# mini-MIDI-Splitter.net
KiCad netlist of a schematic drawn in EAGLE
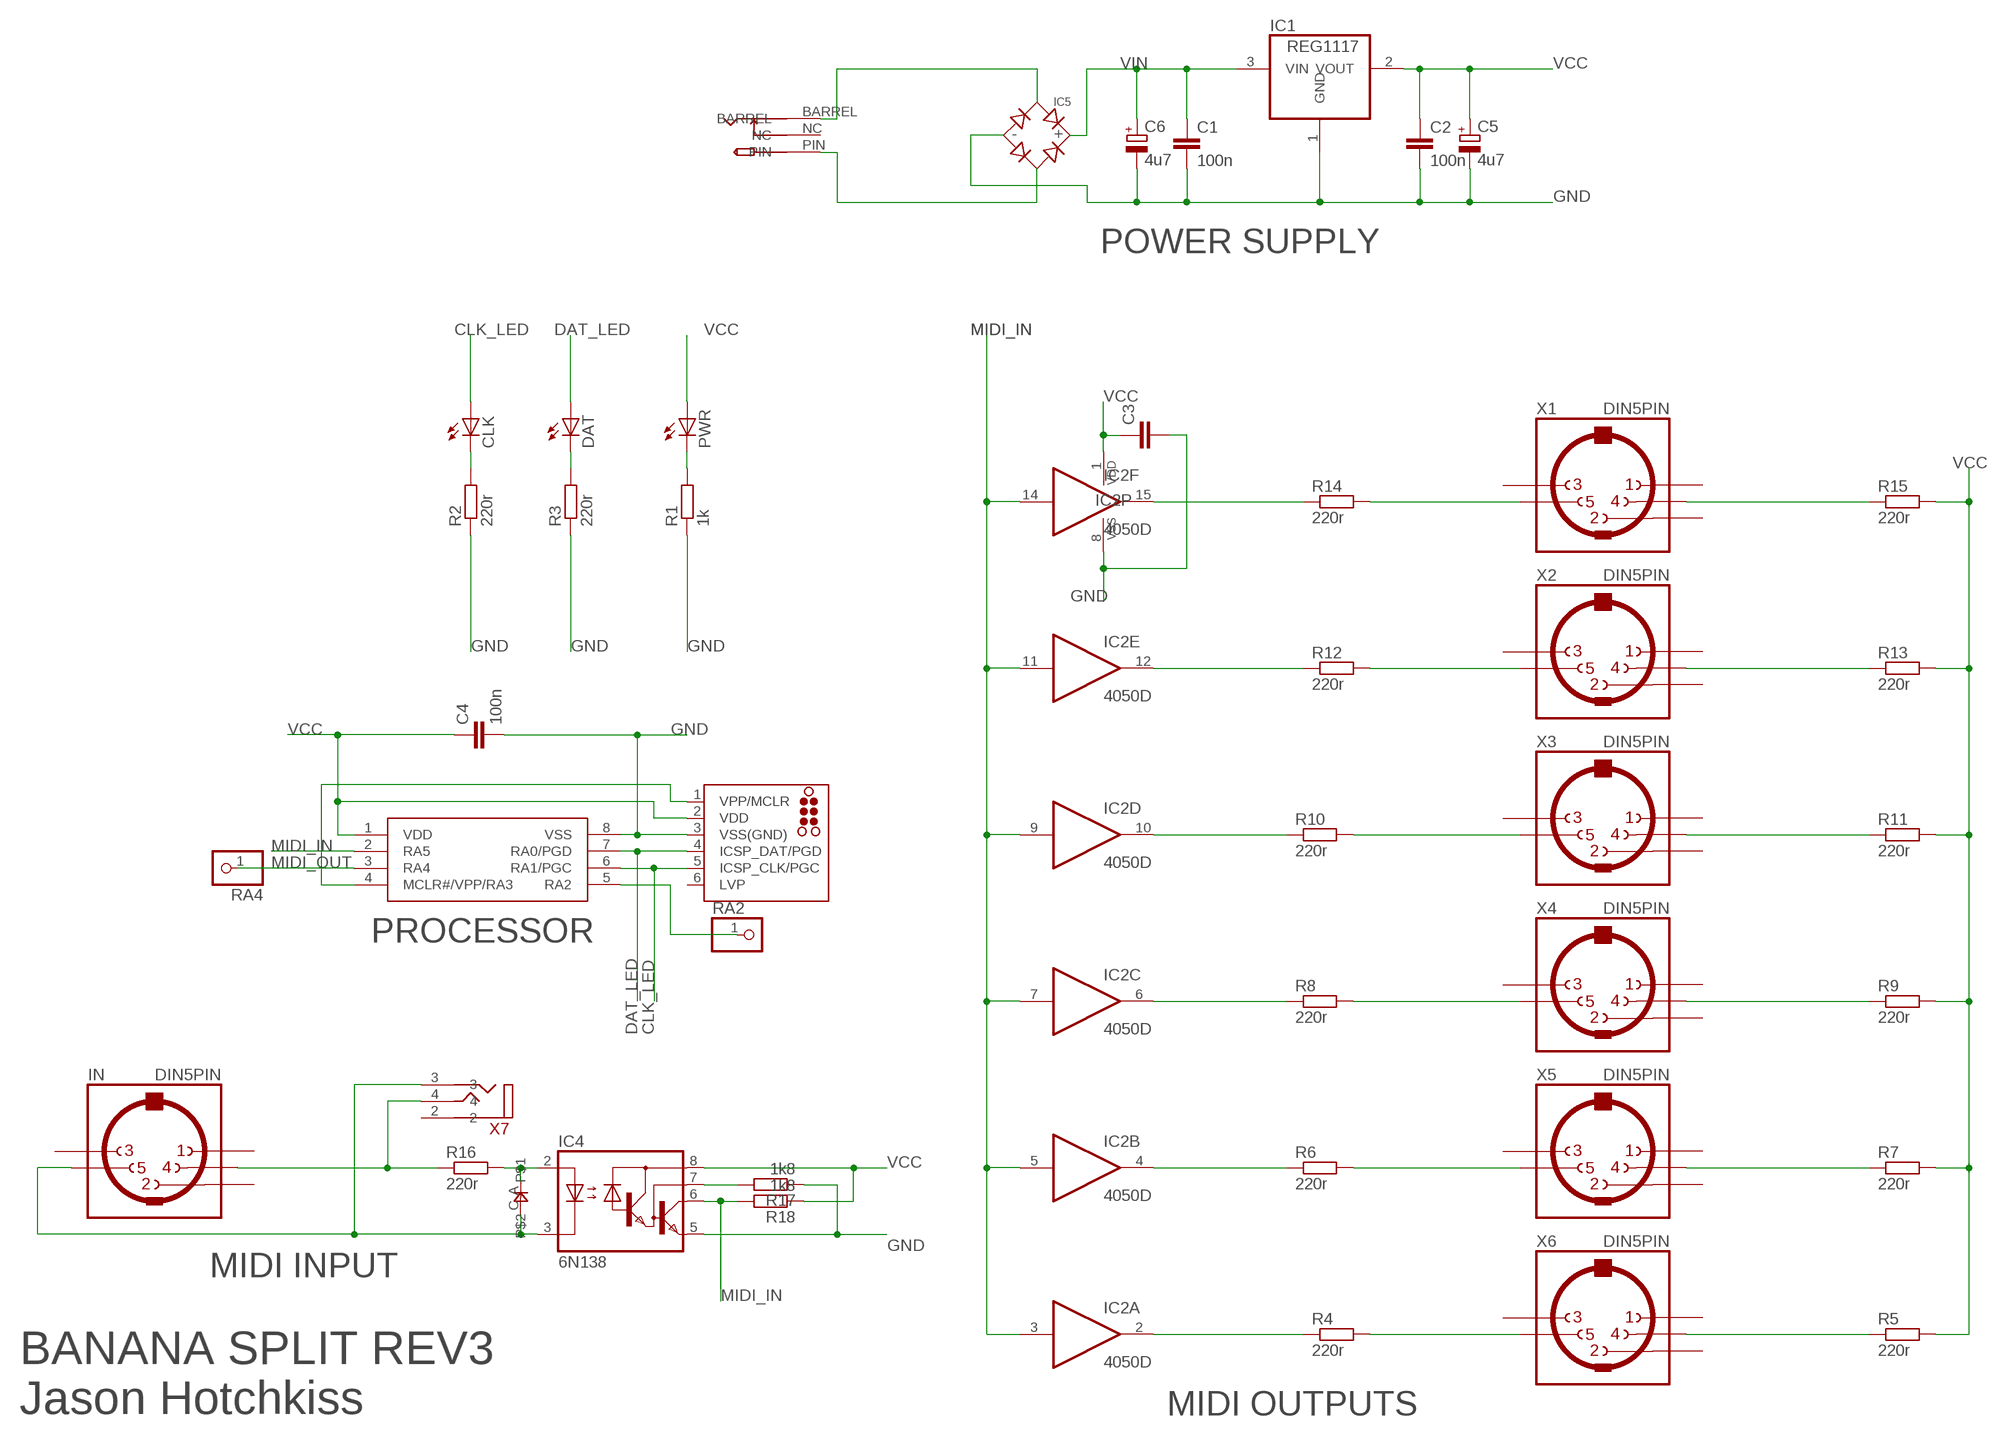
[diagram p0: schematic, sheet 1]

(export (version "E")
  (design (tool "Eeschema 10.0.6"))
  (components
    (comp (ref "C1")
      (value "100n")
      (footprint "eagle-import:C0805")
      (libsource (lib "eagle-import") (part "C-EUC0805"))
    )
    (comp (ref "C2")
      (value "100n")
      (footprint "eagle-import:C0805")
      (libsource (lib "eagle-import") (part "C-EUC0805"))
    )
    (comp (ref "C3")
      (value "C-EUC0805")
      (footprint "eagle-import:C0805")
      (libsource (lib "eagle-import") (part "C-EUC0805"))
    )
    (comp (ref "C4")
      (value "100n")
      (footprint "eagle-import:C0805")
      (libsource (lib "eagle-import") (part "C-EUC0805"))
    )
    (comp (ref "C5")
      (value "4u7")
      (footprint "eagle-import:E2-4")
      (libsource (lib "eagle-import") (part "CPOL-EUE2-4"))
    )
    (comp (ref "C6")
      (value "4u7")
      (footprint "eagle-import:E2-4")
      (libsource (lib "eagle-import") (part "CPOL-EUE2-4"))
    )
    (comp (ref "CLK")
      (value "LED3MM")
      (footprint "eagle-import:LED3MM")
      (libsource (lib "eagle-import") (part "LED3MM"))
    )
    (comp (ref "D1")
      (value "0805DIODE")
      (footprint "eagle-import:0805DIODE")
      (libsource (lib "eagle-import") (part "0805DIODE"))
    )
    (comp (ref "DAT")
      (value "LED3MM")
      (footprint "eagle-import:LED3MM")
      (libsource (lib "eagle-import") (part "LED3MM"))
    )
    (comp (ref "IC1")
      (value "REG1117")
      (footprint "eagle-import:SOT223")
      (libsource (lib "eagle-import") (part "REG1117"))
    )
    (comp (ref "IC2")
      (value "4050D")
      (footprint "eagle-import:SO16")
      (libsource (lib "eagle-import") (part "4050D"))
    )
    (comp (ref "IC3")
      (value "PIC12F1822SO08")
      (footprint "eagle-import:SO08")
      (libsource (lib "eagle-import") (part "PIC12F1822SO08"))
    )
    (comp (ref "IC4")
      (value "6N138")
      (footprint "eagle-import:DIL08")
      (fields (field (name "MF") "VISHAY/TELEFUNKEN"))
      (libsource (lib "eagle-import") (part "6N138"))
    )
    (comp (ref "IC5")
      (value "BRIDGERECTIFIER")
      (footprint "eagle-import:SOIC-4")
      (libsource (lib "eagle-import") (part "BRIDGERECTIFIER"))
    )
    (comp (ref "ICSP")
      (value "TC2030-MCP-NL")
      (footprint "eagle-import:TC2030-MCP-NL")
      (libsource (lib "eagle-import") (part "TC2030-MCP-NL"))
    )
    (comp (ref "IN")
      (value "DIN5PIN")
      (footprint "eagle-import:EDGEDIN")
      (libsource (lib "eagle-import") (part "DIN5PIN"))
    )
    (comp (ref "PWR")
      (value "LED3MM")
      (footprint "eagle-import:LED3MM")
      (libsource (lib "eagle-import") (part "LED3MM"))
    )
    (comp (ref "R1")
      (value "1k")
      (footprint "eagle-import:R0805")
      (libsource (lib "eagle-import") (part "R-EU_R0805"))
    )
    (comp (ref "R2")
      (value "220r")
      (footprint "eagle-import:R0805")
      (libsource (lib "eagle-import") (part "R-EU_R0805"))
    )
    (comp (ref "R3")
      (value "220r")
      (footprint "eagle-import:R0805")
      (libsource (lib "eagle-import") (part "R-EU_R0805"))
    )
    (comp (ref "R4")
      (value "220r")
      (footprint "eagle-import:R0805")
      (libsource (lib "eagle-import") (part "R-EU_R0805"))
    )
    (comp (ref "R5")
      (value "220r")
      (footprint "eagle-import:R0805")
      (libsource (lib "eagle-import") (part "R-EU_R0805"))
    )
    (comp (ref "R6")
      (value "220r")
      (footprint "eagle-import:R0805")
      (libsource (lib "eagle-import") (part "R-EU_R0805"))
    )
    (comp (ref "R7")
      (value "220r")
      (footprint "eagle-import:R0805")
      (libsource (lib "eagle-import") (part "R-EU_R0805"))
    )
    (comp (ref "R8")
      (value "220r")
      (footprint "eagle-import:R0805")
      (libsource (lib "eagle-import") (part "R-EU_R0805"))
    )
    (comp (ref "R9")
      (value "220r")
      (footprint "eagle-import:R0805")
      (libsource (lib "eagle-import") (part "R-EU_R0805"))
    )
    (comp (ref "R10")
      (value "220r")
      (footprint "eagle-import:R0805")
      (libsource (lib "eagle-import") (part "R-EU_R0805"))
    )
    (comp (ref "R11")
      (value "220r")
      (footprint "eagle-import:R0805")
      (libsource (lib "eagle-import") (part "R-EU_R0805"))
    )
    (comp (ref "R12")
      (value "220r")
      (footprint "eagle-import:R0805")
      (libsource (lib "eagle-import") (part "R-EU_R0805"))
    )
    (comp (ref "R13")
      (value "220r")
      (footprint "eagle-import:R0805")
      (libsource (lib "eagle-import") (part "R-EU_R0805"))
    )
    (comp (ref "R14")
      (value "220r")
      (footprint "eagle-import:R0805")
      (libsource (lib "eagle-import") (part "R-EU_R0805"))
    )
    (comp (ref "R15")
      (value "220r")
      (footprint "eagle-import:R0805")
      (libsource (lib "eagle-import") (part "R-EU_R0805"))
    )
    (comp (ref "R16")
      (value "220r")
      (footprint "eagle-import:R0805")
      (libsource (lib "eagle-import") (part "R-EU_R0805"))
    )
    (comp (ref "R17")
      (value "1k8")
      (footprint "eagle-import:R0805")
      (libsource (lib "eagle-import") (part "R-EU_R0805"))
    )
    (comp (ref "R18")
      (value "1k8")
      (footprint "eagle-import:R0805")
      (libsource (lib "eagle-import") (part "R-EU_R0805"))
    )
    (comp (ref "RA2")
      (value "PINHD-1X1")
      (footprint "eagle-import:1X01")
      (libsource (lib "eagle-import") (part "PINHD-1X1"))
    )
    (comp (ref "RA4")
      (value "PINHD-1X1")
      (footprint "eagle-import:1X01")
      (libsource (lib "eagle-import") (part "PINHD-1X1"))
    )
    (comp (ref "U$1")
      (value "PWR_SOCKET_2_1MM")
      (footprint "eagle-import:PWR_SOCKET_2_1MM")
      (libsource (lib "eagle-import") (part "PWR_SOCKET_2_1MM"))
    )
    (comp (ref "X1")
      (value "DIN5PIN")
      (footprint "eagle-import:EDGEDIN")
      (libsource (lib "eagle-import") (part "DIN5PIN"))
    )
    (comp (ref "X2")
      (value "DIN5PIN")
      (footprint "eagle-import:EDGEDIN")
      (libsource (lib "eagle-import") (part "DIN5PIN"))
    )
    (comp (ref "X3")
      (value "DIN5PIN")
      (footprint "eagle-import:EDGEDIN")
      (libsource (lib "eagle-import") (part "DIN5PIN"))
    )
    (comp (ref "X4")
      (value "DIN5PIN")
      (footprint "eagle-import:EDGEDIN")
      (libsource (lib "eagle-import") (part "DIN5PIN"))
    )
    (comp (ref "X5")
      (value "DIN5PIN")
      (footprint "eagle-import:EDGEDIN")
      (libsource (lib "eagle-import") (part "DIN5PIN"))
    )
    (comp (ref "X6")
      (value "DIN5PIN")
      (footprint "eagle-import:EDGEDIN")
      (libsource (lib "eagle-import") (part "DIN5PIN"))
    )
    (comp (ref "X7")
      (value "VERTICAL_3_5MM_SOCKET")
      (footprint "eagle-import:VERTICAL_3_5MM_SOCKET")
      (libsource (lib "eagle-import") (part "VERTICAL_3_5MM_SOCKET"))
    )
  )
  (nets
    (net (code "1") (name "/CLK_LED") (class "Default")
      (node (ref "CLK") (pin "A") (pinfunction "A_A") (pintype "passive"))
      (node (ref "IC3") (pin "6") (pinfunction "RA1/PGC_6") (pintype "bidirectional"))
      (node (ref "ICSP") (pin "5") (pinfunction "ICSP_CLK/PGC_5") (pintype "output"))
    )
    (net (code "2") (name "/DAT_LED") (class "Default")
      (node (ref "DAT") (pin "A") (pinfunction "A_A") (pintype "passive"))
      (node (ref "IC3") (pin "7") (pinfunction "RA0/PGD_7") (pintype "bidirectional"))
      (node (ref "ICSP") (pin "4") (pinfunction "ICSP_DAT/PGD_4") (pintype "bidirectional"))
    )
    (net (code "3") (name "/GND") (class "Default")
      (node (ref "C1") (pin "2") (pinfunction "2_2") (pintype "passive"))
      (node (ref "C2") (pin "2") (pinfunction "2_2") (pintype "passive"))
      (node (ref "C3") (pin "2") (pinfunction "2_2") (pintype "passive"))
      (node (ref "C4") (pin "2") (pinfunction "2_2") (pintype "passive"))
      (node (ref "C5") (pin "-") (pinfunction "-_-") (pintype "passive"))
      (node (ref "C6") (pin "-") (pinfunction "-_-") (pintype "passive"))
      (node (ref "IC1") (pin "1") (pinfunction "GND_1") (pintype "power_in"))
      (node (ref "IC2") (pin "8") (pinfunction "VSS_8") (pintype "power_in"))
      (node (ref "IC3") (pin "8") (pinfunction "VSS_8") (pintype "power_in"))
      (node (ref "IC4") (pin "5") (pinfunction "GND_5") (pintype "passive"))
      (node (ref "IC5") (pin "-") (pinfunction "-_-") (pintype "passive"))
      (node (ref "ICSP") (pin "3") (pinfunction "VSS(GND)_3") (pintype "power_in"))
      (node (ref "R1") (pin "1") (pinfunction "1_1") (pintype "passive"))
      (node (ref "R17") (pin "1") (pinfunction "1_1") (pintype "passive"))
      (node (ref "R2") (pin "1") (pinfunction "1_1") (pintype "passive"))
      (node (ref "R3") (pin "1") (pinfunction "1_1") (pintype "passive"))
    )
    (net (code "4") (name "/MIDI_IN") (class "Default")
      (node (ref "IC2") (pin "11") (pinfunction "I_11") (pintype "input"))
      (node (ref "IC2") (pin "14") (pinfunction "I_14") (pintype "input"))
      (node (ref "IC2") (pin "3") (pinfunction "I_3") (pintype "input"))
      (node (ref "IC2") (pin "5") (pinfunction "I_5") (pintype "input"))
      (node (ref "IC2") (pin "7") (pinfunction "I_7") (pintype "input"))
      (node (ref "IC2") (pin "9") (pinfunction "I_9") (pintype "input"))
      (node (ref "IC3") (pin "2") (pinfunction "RA5_2") (pintype "bidirectional"))
      (node (ref "IC4") (pin "6") (pinfunction "VO_6") (pintype "passive"))
      (node (ref "R18") (pin "2") (pinfunction "2_2") (pintype "passive"))
    )
    (net (code "5") (name "/MIDI_OUT") (class "Default")
      (node (ref "IC3") (pin "3") (pinfunction "RA4_3") (pintype "bidirectional"))
      (node (ref "RA4") (pin "1") (pinfunction "1_1") (pintype "passive"))
    )
    (net (code "6") (name "/VCC") (class "Default")
      (node (ref "C2") (pin "1") (pinfunction "1_1") (pintype "passive"))
      (node (ref "C3") (pin "1") (pinfunction "1_1") (pintype "passive"))
      (node (ref "C4") (pin "1") (pinfunction "1_1") (pintype "passive"))
      (node (ref "C5") (pin "+") (pinfunction "+_+") (pintype "passive"))
      (node (ref "IC1") (pin "2") (pinfunction "VOUT_2") (pintype "output"))
      (node (ref "IC2") (pin "1") (pinfunction "VDD_1") (pintype "power_in"))
      (node (ref "IC3") (pin "1") (pinfunction "VDD_1") (pintype "power_in"))
      (node (ref "IC4") (pin "8") (pinfunction "VCC_8") (pintype "passive"))
      (node (ref "ICSP") (pin "2") (pinfunction "VDD_2") (pintype "power_in"))
      (node (ref "PWR") (pin "A") (pinfunction "A_A") (pintype "passive"))
      (node (ref "R11") (pin "2") (pinfunction "2_2") (pintype "passive"))
      (node (ref "R13") (pin "2") (pinfunction "2_2") (pintype "passive"))
      (node (ref "R15") (pin "2") (pinfunction "2_2") (pintype "passive"))
      (node (ref "R18") (pin "1") (pinfunction "1_1") (pintype "passive"))
      (node (ref "R5") (pin "2") (pinfunction "2_2") (pintype "passive"))
      (node (ref "R7") (pin "2") (pinfunction "2_2") (pintype "passive"))
      (node (ref "R9") (pin "2") (pinfunction "2_2") (pintype "passive"))
    )
    (net (code "7") (name "/VIN") (class "Default")
      (node (ref "C1") (pin "1") (pinfunction "1_1") (pintype "passive"))
      (node (ref "C6") (pin "+") (pinfunction "+_+") (pintype "passive"))
      (node (ref "IC1") (pin "3") (pinfunction "VIN_3") (pintype "input"))
      (node (ref "IC5") (pin "+") (pinfunction "+_+") (pintype "passive"))
    )
    (net (code "8") (name "Net-(CLK-C)") (class "Default")
      (node (ref "CLK") (pin "K") (pinfunction "C_K") (pintype "passive"))
      (node (ref "R2") (pin "2") (pinfunction "2_2") (pintype "passive"))
    )
    (net (code "9") (name "Net-(D1-P$1)") (class "Default")
      (node (ref "D1") (pin "C") (pinfunction "P$1_C") (pintype "bidirectional"))
      (node (ref "IC4") (pin "3") (pinfunction "C_3") (pintype "passive"))
      (node (ref "IN") (pin "5") (pinfunction "5_5") (pintype "passive"))
      (node (ref "X7") (pin "3") (pinfunction "3_3") (pintype "bidirectional"))
    )
    (net (code "10") (name "Net-(D1-P$2)") (class "Default")
      (node (ref "D1") (pin "A") (pinfunction "P$2_A") (pintype "bidirectional"))
      (node (ref "IC4") (pin "2") (pinfunction "A_2") (pintype "passive"))
      (node (ref "R16") (pin "2") (pinfunction "2_2") (pintype "passive"))
    )
    (net (code "11") (name "Net-(DAT-C)") (class "Default")
      (node (ref "DAT") (pin "K") (pinfunction "C_K") (pintype "passive"))
      (node (ref "R3") (pin "2") (pinfunction "2_2") (pintype "passive"))
    )
    (net (code "12") (name "Net-(IC2A-O)") (class "Default")
      (node (ref "IC2") (pin "2") (pinfunction "O_2") (pintype "output"))
      (node (ref "R4") (pin "1") (pinfunction "1_1") (pintype "passive"))
    )
    (net (code "13") (name "Net-(IC2B-O)") (class "Default")
      (node (ref "IC2") (pin "4") (pinfunction "O_4") (pintype "output"))
      (node (ref "R6") (pin "1") (pinfunction "1_1") (pintype "passive"))
    )
    (net (code "14") (name "Net-(IC2C-O)") (class "Default")
      (node (ref "IC2") (pin "6") (pinfunction "O_6") (pintype "output"))
      (node (ref "R8") (pin "1") (pinfunction "1_1") (pintype "passive"))
    )
    (net (code "15") (name "Net-(IC2D-O)") (class "Default")
      (node (ref "IC2") (pin "10") (pinfunction "O_10") (pintype "output"))
      (node (ref "R10") (pin "1") (pinfunction "1_1") (pintype "passive"))
    )
    (net (code "16") (name "Net-(IC2E-O)") (class "Default")
      (node (ref "IC2") (pin "12") (pinfunction "O_12") (pintype "output"))
      (node (ref "R12") (pin "1") (pinfunction "1_1") (pintype "passive"))
    )
    (net (code "17") (name "Net-(IC2F-O)") (class "Default")
      (node (ref "IC2") (pin "15") (pinfunction "O_15") (pintype "output"))
      (node (ref "R14") (pin "1") (pinfunction "1_1") (pintype "passive"))
    )
    (net (code "18") (name "Net-(IC3-MCLR#{slash}VPP{slash}RA3)") (class "Default")
      (node (ref "IC3") (pin "4") (pinfunction "MCLR#/VPP/RA3_4") (pintype "bidirectional"))
      (node (ref "ICSP") (pin "1") (pinfunction "VPP/MCLR_1") (pintype "passive"))
    )
    (net (code "19") (name "Net-(IC3-RA2)") (class "Default")
      (node (ref "IC3") (pin "5") (pinfunction "RA2_5") (pintype "bidirectional"))
      (node (ref "RA2") (pin "1") (pinfunction "1_1") (pintype "passive"))
    )
    (net (code "20") (name "Net-(IC4-VB)") (class "Default")
      (node (ref "IC4") (pin "7") (pinfunction "VB_7") (pintype "passive"))
      (node (ref "R17") (pin "2") (pinfunction "2_2") (pintype "passive"))
    )
    (net (code "21") (name "Net-(IC5-AC1)") (class "Default")
      (node (ref "IC5") (pin "~1") (pinfunction "AC1_~1") (pintype "passive"))
      (node (ref "U$1") (pin "BARREL") (pinfunction "BARREL_BARREL") (pintype "bidirectional"))
    )
    (net (code "22") (name "Net-(IC5-AC2)") (class "Default")
      (node (ref "IC5") (pin "~2") (pinfunction "AC2_~2") (pintype "passive"))
      (node (ref "U$1") (pin "PIN") (pinfunction "PIN_PIN") (pintype "bidirectional"))
    )
    (net (code "23") (name "Net-(IN-Pad4)") (class "Default")
      (node (ref "IN") (pin "4") (pinfunction "4_4") (pintype "passive"))
      (node (ref "R16") (pin "1") (pinfunction "1_1") (pintype "passive"))
      (node (ref "X7") (pin "4") (pinfunction "4_4") (pintype "bidirectional"))
    )
    (net (code "24") (name "Net-(PWR-C)") (class "Default")
      (node (ref "PWR") (pin "K") (pinfunction "C_K") (pintype "passive"))
      (node (ref "R1") (pin "2") (pinfunction "2_2") (pintype "passive"))
    )
    (net (code "25") (name "Net-(R4-Pad2)") (class "Default")
      (node (ref "R4") (pin "2") (pinfunction "2_2") (pintype "passive"))
      (node (ref "X6") (pin "5") (pinfunction "5_5") (pintype "passive"))
    )
    (net (code "26") (name "Net-(R5-Pad1)") (class "Default")
      (node (ref "R5") (pin "1") (pinfunction "1_1") (pintype "passive"))
      (node (ref "X6") (pin "4") (pinfunction "4_4") (pintype "passive"))
    )
    (net (code "27") (name "Net-(R6-Pad2)") (class "Default")
      (node (ref "R6") (pin "2") (pinfunction "2_2") (pintype "passive"))
      (node (ref "X5") (pin "5") (pinfunction "5_5") (pintype "passive"))
    )
    (net (code "28") (name "Net-(R7-Pad1)") (class "Default")
      (node (ref "R7") (pin "1") (pinfunction "1_1") (pintype "passive"))
      (node (ref "X5") (pin "4") (pinfunction "4_4") (pintype "passive"))
    )
    (net (code "29") (name "Net-(R8-Pad2)") (class "Default")
      (node (ref "R8") (pin "2") (pinfunction "2_2") (pintype "passive"))
      (node (ref "X4") (pin "5") (pinfunction "5_5") (pintype "passive"))
    )
    (net (code "30") (name "Net-(R9-Pad1)") (class "Default")
      (node (ref "R9") (pin "1") (pinfunction "1_1") (pintype "passive"))
      (node (ref "X4") (pin "4") (pinfunction "4_4") (pintype "passive"))
    )
    (net (code "31") (name "Net-(R10-Pad2)") (class "Default")
      (node (ref "R10") (pin "2") (pinfunction "2_2") (pintype "passive"))
      (node (ref "X3") (pin "5") (pinfunction "5_5") (pintype "passive"))
    )
    (net (code "32") (name "Net-(R11-Pad1)") (class "Default")
      (node (ref "R11") (pin "1") (pinfunction "1_1") (pintype "passive"))
      (node (ref "X3") (pin "4") (pinfunction "4_4") (pintype "passive"))
    )
    (net (code "33") (name "Net-(R12-Pad2)") (class "Default")
      (node (ref "R12") (pin "2") (pinfunction "2_2") (pintype "passive"))
      (node (ref "X2") (pin "5") (pinfunction "5_5") (pintype "passive"))
    )
    (net (code "34") (name "Net-(R13-Pad1)") (class "Default")
      (node (ref "R13") (pin "1") (pinfunction "1_1") (pintype "passive"))
      (node (ref "X2") (pin "4") (pinfunction "4_4") (pintype "passive"))
    )
    (net (code "35") (name "Net-(R14-Pad2)") (class "Default")
      (node (ref "R14") (pin "2") (pinfunction "2_2") (pintype "passive"))
      (node (ref "X1") (pin "5") (pinfunction "5_5") (pintype "passive"))
    )
    (net (code "36") (name "Net-(R15-Pad1)") (class "Default")
      (node (ref "R15") (pin "1") (pinfunction "1_1") (pintype "passive"))
      (node (ref "X1") (pin "4") (pinfunction "4_4") (pintype "passive"))
    )
    (net (code "37") (name "unconnected-(ICSP-LVP-Pad6)") (class "Default")
      (node (ref "ICSP") (pin "6") (pinfunction "LVP_6") (pintype "bidirectional"))
    )
    (net (code "38") (name "unconnected-(IN-Pad1)") (class "Default")
      (node (ref "IN") (pin "1") (pinfunction "1_1") (pintype "passive"))
    )
    (net (code "39") (name "unconnected-(IN-Pad2)") (class "Default")
      (node (ref "IN") (pin "2") (pinfunction "2_2") (pintype "passive"))
    )
    (net (code "40") (name "unconnected-(IN-Pad3)") (class "Default")
      (node (ref "IN") (pin "3") (pinfunction "3_3") (pintype "passive"))
    )
    (net (code "41") (name "unconnected-(U$1-PadNC)") (class "Default")
      (node (ref "U$1") (pin "NC") (pinfunction "NC_NC") (pintype "bidirectional"))
    )
    (net (code "42") (name "unconnected-(X1-Pad1)") (class "Default")
      (node (ref "X1") (pin "1") (pinfunction "1_1") (pintype "passive"))
    )
    (net (code "43") (name "unconnected-(X1-Pad2)") (class "Default")
      (node (ref "X1") (pin "2") (pinfunction "2_2") (pintype "passive"))
    )
    (net (code "44") (name "unconnected-(X1-Pad3)") (class "Default")
      (node (ref "X1") (pin "3") (pinfunction "3_3") (pintype "passive"))
    )
    (net (code "45") (name "unconnected-(X2-Pad1)") (class "Default")
      (node (ref "X2") (pin "1") (pinfunction "1_1") (pintype "passive"))
    )
    (net (code "46") (name "unconnected-(X2-Pad2)") (class "Default")
      (node (ref "X2") (pin "2") (pinfunction "2_2") (pintype "passive"))
    )
    (net (code "47") (name "unconnected-(X2-Pad3)") (class "Default")
      (node (ref "X2") (pin "3") (pinfunction "3_3") (pintype "passive"))
    )
    (net (code "48") (name "unconnected-(X3-Pad1)") (class "Default")
      (node (ref "X3") (pin "1") (pinfunction "1_1") (pintype "passive"))
    )
    (net (code "49") (name "unconnected-(X3-Pad2)") (class "Default")
      (node (ref "X3") (pin "2") (pinfunction "2_2") (pintype "passive"))
    )
    (net (code "50") (name "unconnected-(X3-Pad3)") (class "Default")
      (node (ref "X3") (pin "3") (pinfunction "3_3") (pintype "passive"))
    )
    (net (code "51") (name "unconnected-(X4-Pad1)") (class "Default")
      (node (ref "X4") (pin "1") (pinfunction "1_1") (pintype "passive"))
    )
    (net (code "52") (name "unconnected-(X4-Pad2)") (class "Default")
      (node (ref "X4") (pin "2") (pinfunction "2_2") (pintype "passive"))
    )
    (net (code "53") (name "unconnected-(X4-Pad3)") (class "Default")
      (node (ref "X4") (pin "3") (pinfunction "3_3") (pintype "passive"))
    )
    (net (code "54") (name "unconnected-(X5-Pad1)") (class "Default")
      (node (ref "X5") (pin "1") (pinfunction "1_1") (pintype "passive"))
    )
    (net (code "55") (name "unconnected-(X5-Pad2)") (class "Default")
      (node (ref "X5") (pin "2") (pinfunction "2_2") (pintype "passive"))
    )
    (net (code "56") (name "unconnected-(X5-Pad3)") (class "Default")
      (node (ref "X5") (pin "3") (pinfunction "3_3") (pintype "passive"))
    )
    (net (code "57") (name "unconnected-(X6-Pad1)") (class "Default")
      (node (ref "X6") (pin "1") (pinfunction "1_1") (pintype "passive"))
    )
    (net (code "58") (name "unconnected-(X6-Pad2)") (class "Default")
      (node (ref "X6") (pin "2") (pinfunction "2_2") (pintype "passive"))
    )
    (net (code "59") (name "unconnected-(X6-Pad3)") (class "Default")
      (node (ref "X6") (pin "3") (pinfunction "3_3") (pintype "passive"))
    )
    (net (code "60") (name "unconnected-(X7-Pad2)") (class "Default")
      (node (ref "X7") (pin "2") (pinfunction "2_2") (pintype "bidirectional"))
    )
  )
)
